# H3_DDR3.net
KiCad netlist of a schematic drawn in Altium Designer
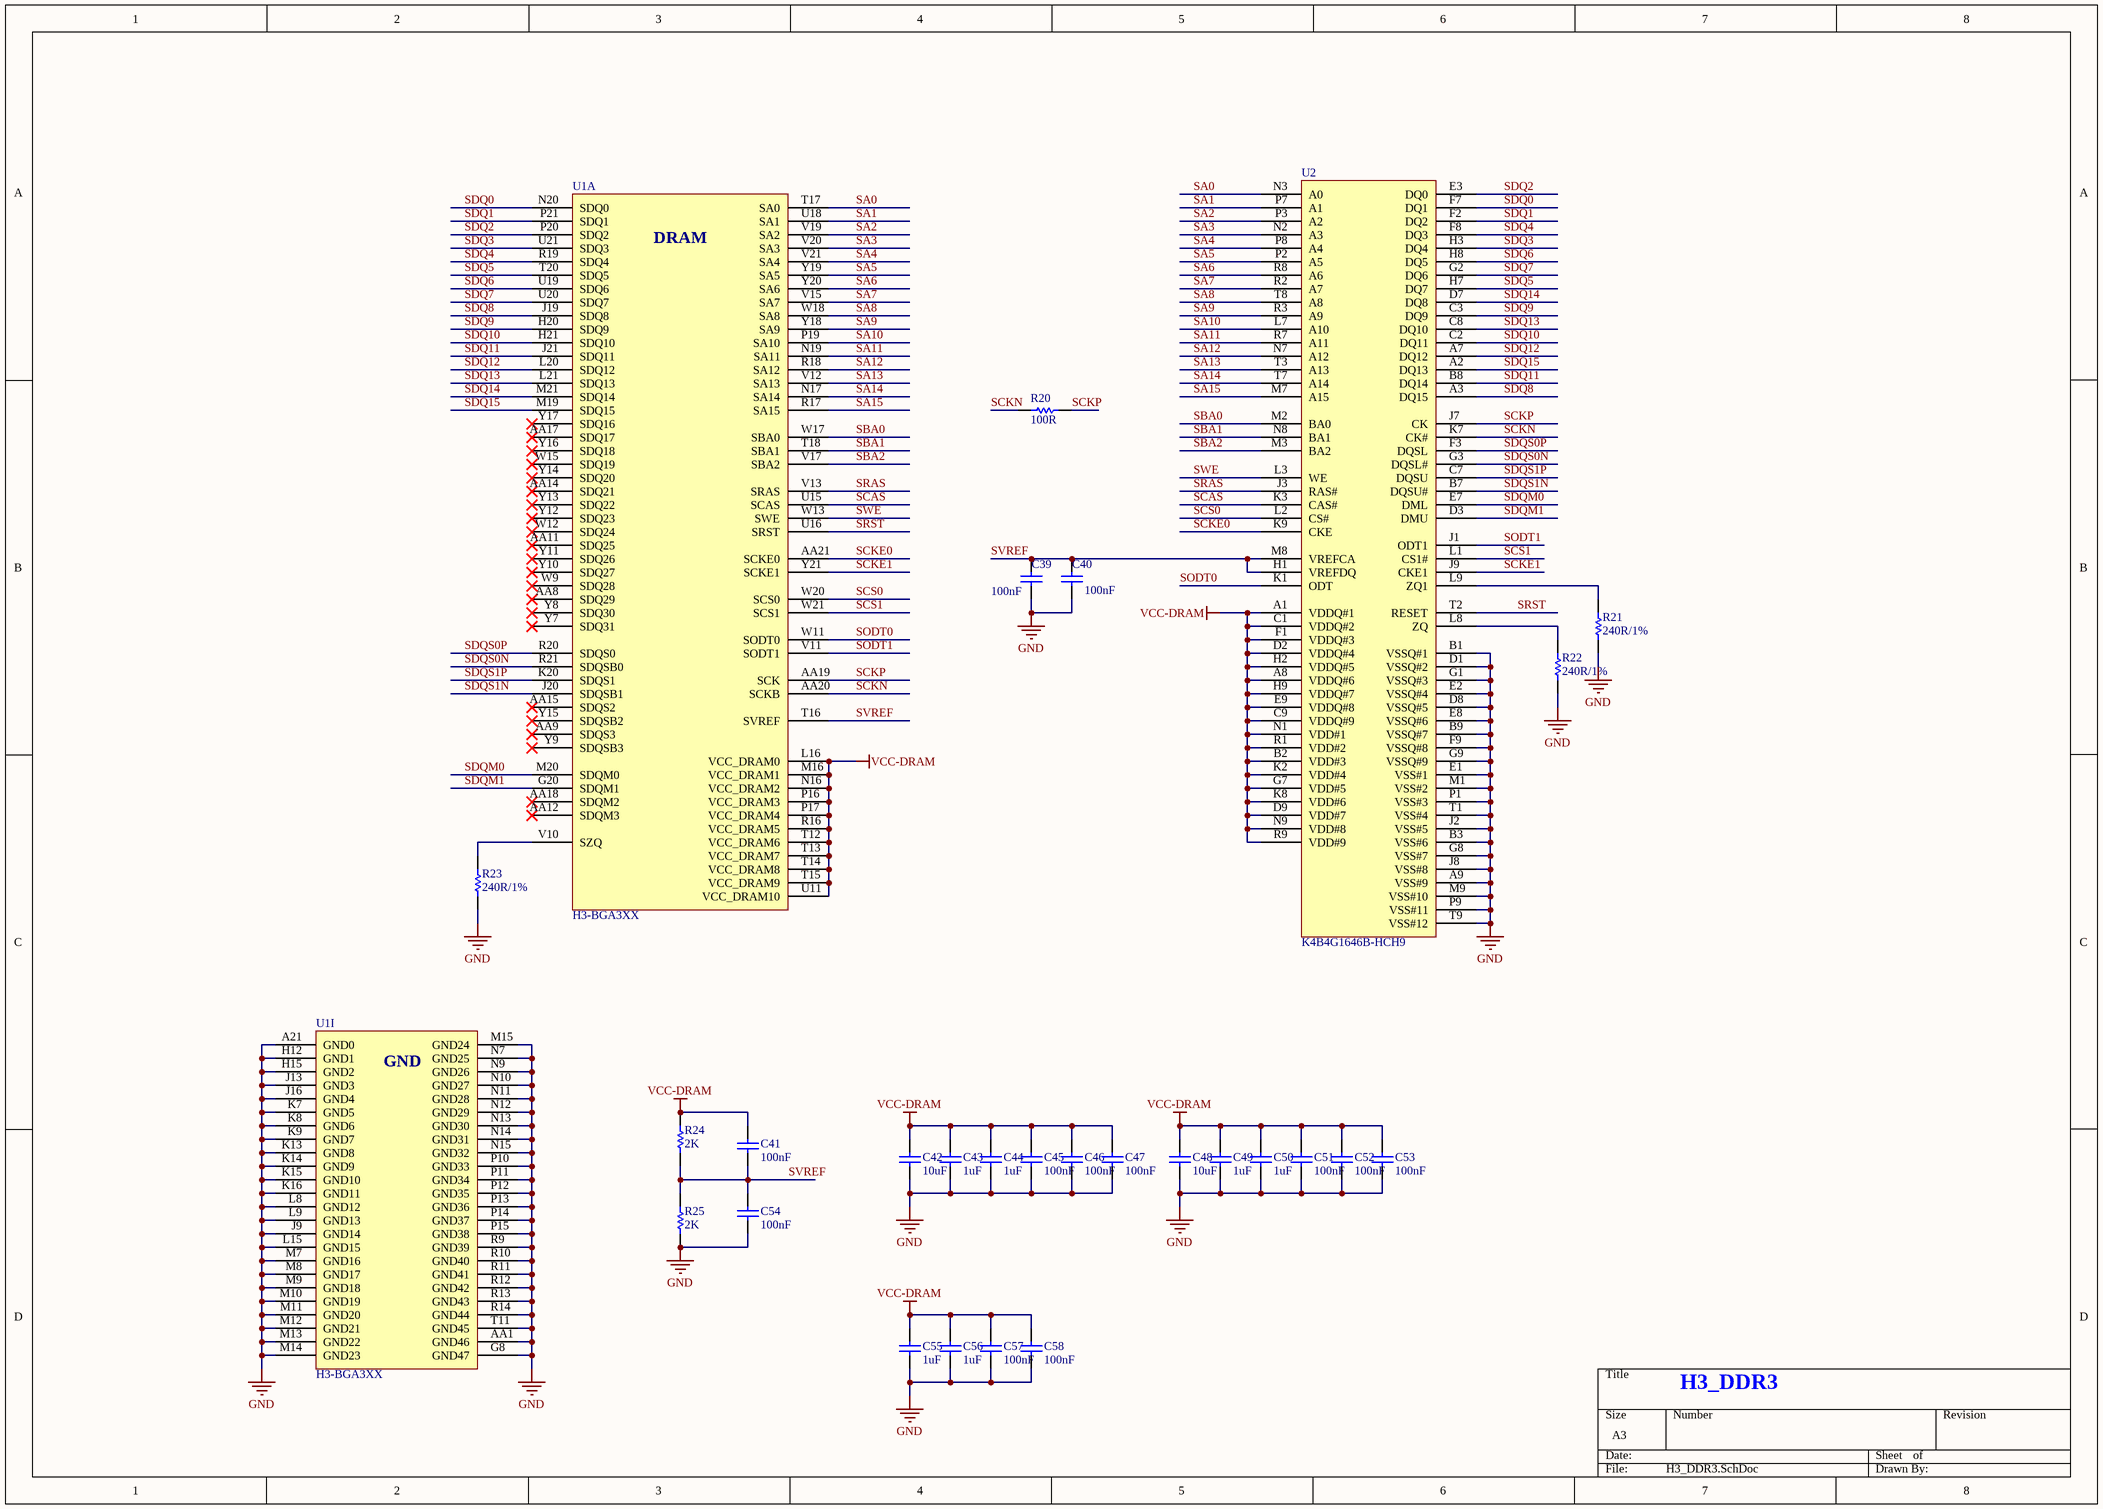
[diagram p0: H3_DDR3.SchDoc]

(export (version "E")
  (design (tool "Eeschema 10.0.6"))
  (components
    (comp (ref "C39")
      (value "100nF")
      (footprint "H3_Core:C0402")
      (description "电容")
      (fields (field (name "PUBLISHER") "Altium Limited"))
      (libsource (lib "Devices") (part "C0402"))
    )
    (comp (ref "C40")
      (value "100nF")
      (footprint "H3_Core:C0402")
      (description "电容")
      (fields (field (name "PUBLISHER") "Altium Limited"))
      (libsource (lib "Devices") (part "C0402"))
    )
    (comp (ref "C41")
      (value "100nF")
      (footprint "H3_Core:C0402")
      (description "电容")
      (fields (field (name "PUBLISHER") "Altium Limited"))
      (libsource (lib "Devices") (part "C0402"))
    )
    (comp (ref "C42")
      (value "10uF")
      (footprint "H3_Core:C0603")
      (description "电容")
      (fields (field (name "PUBLISHER") "Altium Limited"))
      (libsource (lib "Devices") (part "C0603"))
    )
    (comp (ref "C43")
      (value "1uF")
      (footprint "H3_Core:C0402")
      (description "电容")
      (fields (field (name "PUBLISHER") "Altium Limited"))
      (libsource (lib "Devices") (part "C0402"))
    )
    (comp (ref "C44")
      (value "1uF")
      (footprint "H3_Core:C0402")
      (description "电容")
      (fields (field (name "PUBLISHER") "Altium Limited"))
      (libsource (lib "Devices") (part "C0402"))
    )
    (comp (ref "C45")
      (value "100nF")
      (footprint "H3_Core:C0402")
      (description "电容")
      (fields (field (name "PUBLISHER") "Altium Limited"))
      (libsource (lib "Devices") (part "C0402"))
    )
    (comp (ref "C46")
      (value "100nF")
      (footprint "H3_Core:C0402")
      (description "电容")
      (fields (field (name "PUBLISHER") "Altium Limited"))
      (libsource (lib "Devices") (part "C0402"))
    )
    (comp (ref "C47")
      (value "100nF")
      (footprint "H3_Core:C0402")
      (description "电容")
      (fields (field (name "PUBLISHER") "Altium Limited"))
      (libsource (lib "Devices") (part "C0402"))
    )
    (comp (ref "C48")
      (value "10uF")
      (footprint "H3_Core:C0603")
      (description "电容")
      (fields (field (name "PUBLISHER") "Altium Limited"))
      (libsource (lib "Devices") (part "C0603"))
    )
    (comp (ref "C49")
      (value "1uF")
      (footprint "H3_Core:C0402")
      (description "电容")
      (fields (field (name "PUBLISHER") "Altium Limited"))
      (libsource (lib "Devices") (part "C0402"))
    )
    (comp (ref "C50")
      (value "1uF")
      (footprint "H3_Core:C0402")
      (description "电容")
      (fields (field (name "PUBLISHER") "Altium Limited"))
      (libsource (lib "Devices") (part "C0402"))
    )
    (comp (ref "C51")
      (value "100nF")
      (footprint "H3_Core:C0402")
      (description "电容")
      (fields (field (name "PUBLISHER") "Altium Limited"))
      (libsource (lib "Devices") (part "C0402"))
    )
    (comp (ref "C52")
      (value "100nF")
      (footprint "H3_Core:C0402")
      (description "电容")
      (fields (field (name "PUBLISHER") "Altium Limited"))
      (libsource (lib "Devices") (part "C0402"))
    )
    (comp (ref "C53")
      (value "100nF")
      (footprint "H3_Core:C0402")
      (description "电容")
      (fields (field (name "PUBLISHER") "Altium Limited"))
      (libsource (lib "Devices") (part "C0402"))
    )
    (comp (ref "C54")
      (value "100nF")
      (footprint "H3_Core:C0402")
      (description "电容")
      (fields (field (name "PUBLISHER") "Altium Limited"))
      (libsource (lib "Devices") (part "C0402"))
    )
    (comp (ref "C55")
      (value "1uF")
      (footprint "H3_Core:C0402")
      (description "电容")
      (fields (field (name "PUBLISHER") "Altium Limited"))
      (libsource (lib "Devices") (part "C0402"))
    )
    (comp (ref "C56")
      (value "1uF")
      (footprint "H3_Core:C0402")
      (description "电容")
      (fields (field (name "PUBLISHER") "Altium Limited"))
      (libsource (lib "Devices") (part "C0402"))
    )
    (comp (ref "C57")
      (value "100nF")
      (footprint "H3_Core:C0402")
      (description "电容")
      (fields (field (name "PUBLISHER") "Altium Limited"))
      (libsource (lib "Devices") (part "C0402"))
    )
    (comp (ref "C58")
      (value "100nF")
      (footprint "H3_Core:C0402")
      (description "电容")
      (fields (field (name "PUBLISHER") "Altium Limited"))
      (libsource (lib "Devices") (part "C0402"))
    )
    (comp (ref "R20")
      (value "100R")
      (footprint "H3_Core:R0402")
      (description "电阻")
      (fields (field (name "PUBLISHER") "Altium Limited"))
      (libsource (lib "Devices") (part "RES0402"))
    )
    (comp (ref "R21")
      (value "240R/1%")
      (footprint "H3_Core:R0402")
      (description "电阻")
      (fields (field (name "PUBLISHER") "Altium Limited"))
      (libsource (lib "Devices") (part "RES0402"))
    )
    (comp (ref "R22")
      (value "240R/1%")
      (footprint "H3_Core:R0402")
      (description "电阻")
      (fields (field (name "PUBLISHER") "Altium Limited"))
      (libsource (lib "Devices") (part "RES0402"))
    )
    (comp (ref "R23")
      (value "240R/1%")
      (footprint "H3_Core:R0402")
      (description "电阻")
      (fields (field (name "PUBLISHER") "Altium Limited"))
      (libsource (lib "Devices") (part "RES0402"))
    )
    (comp (ref "R24")
      (value "2K")
      (footprint "H3_Core:R0402")
      (description "电阻")
      (fields (field (name "PUBLISHER") "Altium Limited"))
      (libsource (lib "Devices") (part "RES0402"))
    )
    (comp (ref "R25")
      (value "2K")
      (footprint "H3_Core:R0402")
      (description "电阻")
      (fields (field (name "PUBLISHER") "Altium Limited"))
      (libsource (lib "Devices") (part "RES0402"))
    )
    (comp (ref "U1") (value "H3-BGA3XX") (footprint "BGA-H3-347") (libsource (lib "IC") (part "H3-BGA3XX")))
    (comp (ref "U2")
      (value "K4B4G1646B-HCH9")
      (footprint "FBGA-96")
      (libsource (lib "IC") (part "K4B4G1646B-HCH9"))
    )
  )
  (nets
    (net (code "1") (name "/SA0") (class "Default")
      (node (ref "U1") (pin "T17") (pinfunction "SA0_T17") (pintype "passive"))
      (node (ref "U2") (pin "N3") (pinfunction "A0_N3") (pintype "passive"))
    )
    (net (code "2") (name "/SA1") (class "Default")
      (node (ref "U1") (pin "U18") (pinfunction "SA1_U18") (pintype "passive"))
      (node (ref "U2") (pin "P7") (pinfunction "A1_P7") (pintype "passive"))
    )
    (net (code "3") (name "/SA2") (class "Default")
      (node (ref "U1") (pin "V19") (pinfunction "SA2_V19") (pintype "passive"))
      (node (ref "U2") (pin "P3") (pinfunction "A2_P3") (pintype "passive"))
    )
    (net (code "4") (name "/SA3") (class "Default")
      (node (ref "U1") (pin "V20") (pinfunction "SA3_V20") (pintype "passive"))
      (node (ref "U2") (pin "N2") (pinfunction "A3_N2") (pintype "passive"))
    )
    (net (code "5") (name "/SA4") (class "Default")
      (node (ref "U1") (pin "V21") (pinfunction "SA4_V21") (pintype "passive"))
      (node (ref "U2") (pin "P8") (pinfunction "A4_P8") (pintype "passive"))
    )
    (net (code "6") (name "/SA5") (class "Default")
      (node (ref "U1") (pin "Y19") (pinfunction "SA5_Y19") (pintype "passive"))
      (node (ref "U2") (pin "P2") (pinfunction "A5_P2") (pintype "passive"))
    )
    (net (code "7") (name "/SA6") (class "Default")
      (node (ref "U1") (pin "Y20") (pinfunction "SA6_Y20") (pintype "passive"))
      (node (ref "U2") (pin "R8") (pinfunction "A6_R8") (pintype "passive"))
    )
    (net (code "8") (name "/SA7") (class "Default")
      (node (ref "U1") (pin "V15") (pinfunction "SA7_V15") (pintype "passive"))
      (node (ref "U2") (pin "R2") (pinfunction "A7_R2") (pintype "passive"))
    )
    (net (code "9") (name "/SA8") (class "Default")
      (node (ref "U1") (pin "W18") (pinfunction "SA8_W18") (pintype "passive"))
      (node (ref "U2") (pin "T8") (pinfunction "A8_T8") (pintype "passive"))
    )
    (net (code "10") (name "/SA9") (class "Default")
      (node (ref "U1") (pin "Y18") (pinfunction "SA9_Y18") (pintype "passive"))
      (node (ref "U2") (pin "R3") (pinfunction "A9_R3") (pintype "passive"))
    )
    (net (code "11") (name "/SA10") (class "Default")
      (node (ref "U1") (pin "P19") (pinfunction "SA10_P19") (pintype "passive"))
      (node (ref "U2") (pin "L7") (pinfunction "A10_L7") (pintype "passive"))
    )
    (net (code "12") (name "/SA11") (class "Default")
      (node (ref "U1") (pin "N19") (pinfunction "SA11_N19") (pintype "passive"))
      (node (ref "U2") (pin "R7") (pinfunction "A11_R7") (pintype "passive"))
    )
    (net (code "13") (name "/SA12") (class "Default")
      (node (ref "U1") (pin "R18") (pinfunction "SA12_R18") (pintype "passive"))
      (node (ref "U2") (pin "N7") (pinfunction "A12_N7") (pintype "passive"))
    )
    (net (code "14") (name "/SA13") (class "Default")
      (node (ref "U1") (pin "V12") (pinfunction "SA13_V12") (pintype "passive"))
      (node (ref "U2") (pin "T3") (pinfunction "A13_T3") (pintype "passive"))
    )
    (net (code "15") (name "/SA14") (class "Default")
      (node (ref "U1") (pin "N17") (pinfunction "SA14_N17") (pintype "passive"))
      (node (ref "U2") (pin "T7") (pinfunction "A14_T7") (pintype "passive"))
    )
    (net (code "16") (name "/SA15") (class "Default")
      (node (ref "U1") (pin "R17") (pinfunction "SA15_R17") (pintype "passive"))
      (node (ref "U2") (pin "M7") (pinfunction "A15_M7") (pintype "passive"))
    )
    (net (code "17") (name "/SBA0") (class "Default")
      (node (ref "U1") (pin "W17") (pinfunction "SBA0_W17") (pintype "passive"))
      (node (ref "U2") (pin "M2") (pinfunction "BA0_M2") (pintype "passive"))
    )
    (net (code "18") (name "/SBA1") (class "Default")
      (node (ref "U1") (pin "T18") (pinfunction "SBA1_T18") (pintype "passive"))
      (node (ref "U2") (pin "N8") (pinfunction "BA1_N8") (pintype "passive"))
    )
    (net (code "19") (name "/SBA2") (class "Default")
      (node (ref "U1") (pin "V17") (pinfunction "SBA2_V17") (pintype "passive"))
      (node (ref "U2") (pin "M3") (pinfunction "BA2_M3") (pintype "passive"))
    )
    (net (code "20") (name "/SCAS") (class "Default")
      (node (ref "U1") (pin "U15") (pinfunction "SCAS_U15") (pintype "passive"))
      (node (ref "U2") (pin "K3") (pinfunction "CAS#_K3") (pintype "passive"))
    )
    (net (code "21") (name "/SCKE0") (class "Default")
      (node (ref "U1") (pin "AA21") (pinfunction "SCKE0_AA21") (pintype "passive"))
      (node (ref "U2") (pin "K9") (pinfunction "CKE_K9") (pintype "passive"))
    )
    (net (code "22") (name "/SCKE1") (class "Default")
      (node (ref "U1") (pin "Y21") (pinfunction "SCKE1_Y21") (pintype "passive"))
      (node (ref "U2") (pin "J9") (pinfunction "CKE1_J9") (pintype "passive"))
    )
    (net (code "23") (name "/SCKN") (class "Default")
      (node (ref "R20") (pin "2") (pinfunction "2_2") (pintype "passive"))
      (node (ref "U1") (pin "AA20") (pinfunction "SCKB_AA20") (pintype "passive"))
      (node (ref "U2") (pin "K7") (pinfunction "CK#_K7") (pintype "passive"))
    )
    (net (code "24") (name "/SCKP") (class "Default")
      (node (ref "R20") (pin "1") (pinfunction "1_1") (pintype "passive"))
      (node (ref "U1") (pin "AA19") (pinfunction "SCK_AA19") (pintype "passive"))
      (node (ref "U2") (pin "J7") (pinfunction "CK_J7") (pintype "passive"))
    )
    (net (code "25") (name "/SCS0") (class "Default")
      (node (ref "U1") (pin "W20") (pinfunction "SCS0_W20") (pintype "passive"))
      (node (ref "U2") (pin "L2") (pinfunction "CS#_L2") (pintype "passive"))
    )
    (net (code "26") (name "/SCS1") (class "Default")
      (node (ref "U1") (pin "W21") (pinfunction "SCS1_W21") (pintype "passive"))
      (node (ref "U2") (pin "L1") (pinfunction "CS1#_L1") (pintype "passive"))
    )
    (net (code "27") (name "/SDQ0") (class "Default")
      (node (ref "U1") (pin "N20") (pinfunction "SDQ0_N20") (pintype "passive"))
      (node (ref "U2") (pin "F7") (pinfunction "DQ1_F7") (pintype "passive"))
    )
    (net (code "28") (name "/SDQ1") (class "Default")
      (node (ref "U1") (pin "P21") (pinfunction "SDQ1_P21") (pintype "passive"))
      (node (ref "U2") (pin "F2") (pinfunction "DQ2_F2") (pintype "passive"))
    )
    (net (code "29") (name "/SDQ2") (class "Default")
      (node (ref "U1") (pin "P20") (pinfunction "SDQ2_P20") (pintype "passive"))
      (node (ref "U2") (pin "E3") (pinfunction "DQ0_E3") (pintype "passive"))
    )
    (net (code "30") (name "/SDQ3") (class "Default")
      (node (ref "U1") (pin "U21") (pinfunction "SDQ3_U21") (pintype "passive"))
      (node (ref "U2") (pin "H3") (pinfunction "DQ4_H3") (pintype "passive"))
    )
    (net (code "31") (name "/SDQ4") (class "Default")
      (node (ref "U1") (pin "R19") (pinfunction "SDQ4_R19") (pintype "passive"))
      (node (ref "U2") (pin "F8") (pinfunction "DQ3_F8") (pintype "passive"))
    )
    (net (code "32") (name "/SDQ5") (class "Default")
      (node (ref "U1") (pin "T20") (pinfunction "SDQ5_T20") (pintype "passive"))
      (node (ref "U2") (pin "H7") (pinfunction "DQ7_H7") (pintype "passive"))
    )
    (net (code "33") (name "/SDQ6") (class "Default")
      (node (ref "U1") (pin "U19") (pinfunction "SDQ6_U19") (pintype "passive"))
      (node (ref "U2") (pin "H8") (pinfunction "DQ5_H8") (pintype "passive"))
    )
    (net (code "34") (name "/SDQ7") (class "Default")
      (node (ref "U1") (pin "U20") (pinfunction "SDQ7_U20") (pintype "passive"))
      (node (ref "U2") (pin "G2") (pinfunction "DQ6_G2") (pintype "passive"))
    )
    (net (code "35") (name "/SDQ8") (class "Default")
      (node (ref "U1") (pin "J19") (pinfunction "SDQ8_J19") (pintype "passive"))
      (node (ref "U2") (pin "A3") (pinfunction "DQ15_A3") (pintype "passive"))
    )
    (net (code "36") (name "/SDQ9") (class "Default")
      (node (ref "U1") (pin "H20") (pinfunction "SDQ9_H20") (pintype "passive"))
      (node (ref "U2") (pin "C3") (pinfunction "DQ9_C3") (pintype "passive"))
    )
    (net (code "37") (name "/SDQ10") (class "Default")
      (node (ref "U1") (pin "H21") (pinfunction "SDQ10_H21") (pintype "passive"))
      (node (ref "U2") (pin "C2") (pinfunction "DQ11_C2") (pintype "passive"))
    )
    (net (code "38") (name "/SDQ11") (class "Default")
      (node (ref "U1") (pin "J21") (pinfunction "SDQ11_J21") (pintype "passive"))
      (node (ref "U2") (pin "B8") (pinfunction "DQ14_B8") (pintype "passive"))
    )
    (net (code "39") (name "/SDQ12") (class "Default")
      (node (ref "U1") (pin "L20") (pinfunction "SDQ12_L20") (pintype "passive"))
      (node (ref "U2") (pin "A7") (pinfunction "DQ12_A7") (pintype "passive"))
    )
    (net (code "40") (name "/SDQ13") (class "Default")
      (node (ref "U1") (pin "L21") (pinfunction "SDQ13_L21") (pintype "passive"))
      (node (ref "U2") (pin "C8") (pinfunction "DQ10_C8") (pintype "passive"))
    )
    (net (code "41") (name "/SDQ14") (class "Default")
      (node (ref "U1") (pin "M21") (pinfunction "SDQ14_M21") (pintype "passive"))
      (node (ref "U2") (pin "D7") (pinfunction "DQ8_D7") (pintype "passive"))
    )
    (net (code "42") (name "/SDQ15") (class "Default")
      (node (ref "U1") (pin "M19") (pinfunction "SDQ15_M19") (pintype "passive"))
      (node (ref "U2") (pin "A2") (pinfunction "DQ13_A2") (pintype "passive"))
    )
    (net (code "43") (name "/SDQM0") (class "Default")
      (node (ref "U1") (pin "M20") (pinfunction "SDQM0_M20") (pintype "passive"))
      (node (ref "U2") (pin "E7") (pinfunction "DML_E7") (pintype "passive"))
    )
    (net (code "44") (name "/SDQM1") (class "Default")
      (node (ref "U1") (pin "G20") (pinfunction "SDQM1_G20") (pintype "passive"))
      (node (ref "U2") (pin "D3") (pinfunction "DMU_D3") (pintype "passive"))
    )
    (net (code "45") (name "/SDQS0N") (class "Default")
      (node (ref "U1") (pin "R21") (pinfunction "SDQSB0_R21") (pintype "passive"))
      (node (ref "U2") (pin "G3") (pinfunction "DQSL#_G3") (pintype "passive"))
    )
    (net (code "46") (name "/SDQS0P") (class "Default")
      (node (ref "U1") (pin "R20") (pinfunction "SDQS0_R20") (pintype "passive"))
      (node (ref "U2") (pin "F3") (pinfunction "DQSL_F3") (pintype "passive"))
    )
    (net (code "47") (name "/SDQS1N") (class "Default")
      (node (ref "U1") (pin "J20") (pinfunction "SDQSB1_J20") (pintype "passive"))
      (node (ref "U2") (pin "B7") (pinfunction "DQSU#_B7") (pintype "passive"))
    )
    (net (code "48") (name "/SDQS1P") (class "Default")
      (node (ref "U1") (pin "K20") (pinfunction "SDQS1_K20") (pintype "passive"))
      (node (ref "U2") (pin "C7") (pinfunction "DQSU_C7") (pintype "passive"))
    )
    (net (code "49") (name "/SODT0") (class "Default")
      (node (ref "U1") (pin "W11") (pinfunction "SODT0_W11") (pintype "passive"))
      (node (ref "U2") (pin "K1") (pinfunction "ODT_K1") (pintype "passive"))
    )
    (net (code "50") (name "/SODT1") (class "Default")
      (node (ref "U1") (pin "V11") (pinfunction "SODT1_V11") (pintype "passive"))
      (node (ref "U2") (pin "J1") (pinfunction "ODT1_J1") (pintype "passive"))
    )
    (net (code "51") (name "/SRAS") (class "Default")
      (node (ref "U1") (pin "V13") (pinfunction "SRAS_V13") (pintype "passive"))
      (node (ref "U2") (pin "J3") (pinfunction "RAS#_J3") (pintype "passive"))
    )
    (net (code "52") (name "/SRST") (class "Default")
      (node (ref "U1") (pin "U16") (pinfunction "SRST_U16") (pintype "passive"))
      (node (ref "U2") (pin "T2") (pinfunction "RESET_T2") (pintype "passive"))
    )
    (net (code "53") (name "/SVREF") (class "Default")
      (node (ref "C39") (pin "2") (pinfunction "2_2") (pintype "passive"))
      (node (ref "C40") (pin "2") (pinfunction "2_2") (pintype "passive"))
      (node (ref "C41") (pin "1") (pinfunction "1_1") (pintype "passive"))
      (node (ref "C54") (pin "2") (pinfunction "2_2") (pintype "passive"))
      (node (ref "R24") (pin "2") (pinfunction "2_2") (pintype "passive"))
      (node (ref "R25") (pin "1") (pinfunction "1_1") (pintype "passive"))
      (node (ref "U1") (pin "T16") (pinfunction "SVREF_T16") (pintype "passive"))
      (node (ref "U2") (pin "H1") (pinfunction "VREFDQ_H1") (pintype "passive"))
      (node (ref "U2") (pin "M8") (pinfunction "VREFCA_M8") (pintype "passive"))
    )
    (net (code "54") (name "/SWE") (class "Default")
      (node (ref "U1") (pin "W13") (pinfunction "SWE_W13") (pintype "passive"))
      (node (ref "U2") (pin "L3") (pinfunction "WE_L3") (pintype "passive"))
    )
    (net (code "55") (name "GND") (class "Default")
      (node (ref "C39") (pin "1") (pinfunction "1_1") (pintype "passive"))
      (node (ref "C40") (pin "1") (pinfunction "1_1") (pintype "passive"))
      (node (ref "C42") (pin "1") (pinfunction "1_1") (pintype "passive"))
      (node (ref "C43") (pin "1") (pinfunction "1_1") (pintype "passive"))
      (node (ref "C44") (pin "1") (pinfunction "1_1") (pintype "passive"))
      (node (ref "C45") (pin "1") (pinfunction "1_1") (pintype "passive"))
      (node (ref "C46") (pin "1") (pinfunction "1_1") (pintype "passive"))
      (node (ref "C47") (pin "1") (pinfunction "1_1") (pintype "passive"))
      (node (ref "C48") (pin "1") (pinfunction "1_1") (pintype "passive"))
      (node (ref "C49") (pin "1") (pinfunction "1_1") (pintype "passive"))
      (node (ref "C50") (pin "1") (pinfunction "1_1") (pintype "passive"))
      (node (ref "C51") (pin "1") (pinfunction "1_1") (pintype "passive"))
      (node (ref "C52") (pin "1") (pinfunction "1_1") (pintype "passive"))
      (node (ref "C53") (pin "1") (pinfunction "1_1") (pintype "passive"))
      (node (ref "C54") (pin "1") (pinfunction "1_1") (pintype "passive"))
      (node (ref "C55") (pin "1") (pinfunction "1_1") (pintype "passive"))
      (node (ref "C56") (pin "1") (pinfunction "1_1") (pintype "passive"))
      (node (ref "C57") (pin "1") (pinfunction "1_1") (pintype "passive"))
      (node (ref "C58") (pin "1") (pinfunction "1_1") (pintype "passive"))
      (node (ref "R21") (pin "1") (pinfunction "1_1") (pintype "passive"))
      (node (ref "R22") (pin "1") (pinfunction "1_1") (pintype "passive"))
      (node (ref "R23") (pin "1") (pinfunction "1_1") (pintype "passive"))
      (node (ref "R25") (pin "2") (pinfunction "2_2") (pintype "passive"))
      (node (ref "U1") (pin "A21") (pinfunction "GND0_A21") (pintype "passive"))
      (node (ref "U1") (pin "AA1") (pinfunction "GND46_AA1") (pintype "passive"))
      (node (ref "U1") (pin "G8") (pinfunction "GND47_G8") (pintype "passive"))
      (node (ref "U1") (pin "H12") (pinfunction "GND1_H12") (pintype "passive"))
      (node (ref "U1") (pin "H15") (pinfunction "GND2_H15") (pintype "passive"))
      (node (ref "U1") (pin "J13") (pinfunction "GND3_J13") (pintype "passive"))
      (node (ref "U1") (pin "J16") (pinfunction "GND4_J16") (pintype "passive"))
      (node (ref "U1") (pin "J9") (pinfunction "GND14_J9") (pintype "passive"))
      (node (ref "U1") (pin "K13") (pinfunction "GND8_K13") (pintype "passive"))
      (node (ref "U1") (pin "K14") (pinfunction "GND9_K14") (pintype "passive"))
      (node (ref "U1") (pin "K15") (pinfunction "GND10_K15") (pintype "passive"))
      (node (ref "U1") (pin "K16") (pinfunction "GND11_K16") (pintype "passive"))
      (node (ref "U1") (pin "K7") (pinfunction "GND5_K7") (pintype "passive"))
      (node (ref "U1") (pin "K8") (pinfunction "GND6_K8") (pintype "passive"))
      (node (ref "U1") (pin "K9") (pinfunction "GND7_K9") (pintype "passive"))
      (node (ref "U1") (pin "L15") (pinfunction "GND15_L15") (pintype "passive"))
      (node (ref "U1") (pin "L8") (pinfunction "GND12_L8") (pintype "passive"))
      (node (ref "U1") (pin "L9") (pinfunction "GND13_L9") (pintype "passive"))
      (node (ref "U1") (pin "M10") (pinfunction "GND19_M10") (pintype "passive"))
      (node (ref "U1") (pin "M11") (pinfunction "GND20_M11") (pintype "passive"))
      (node (ref "U1") (pin "M12") (pinfunction "GND21_M12") (pintype "passive"))
      (node (ref "U1") (pin "M13") (pinfunction "GND22_M13") (pintype "passive"))
      (node (ref "U1") (pin "M14") (pinfunction "GND23_M14") (pintype "passive"))
      (node (ref "U1") (pin "M15") (pinfunction "GND24_M15") (pintype "passive"))
      (node (ref "U1") (pin "M7") (pinfunction "GND16_M7") (pintype "passive"))
      (node (ref "U1") (pin "M8") (pinfunction "GND17_M8") (pintype "passive"))
      (node (ref "U1") (pin "M9") (pinfunction "GND18_M9") (pintype "passive"))
      (node (ref "U1") (pin "N10") (pinfunction "GND27_N10") (pintype "passive"))
      (node (ref "U1") (pin "N11") (pinfunction "GND28_N11") (pintype "passive"))
      (node (ref "U1") (pin "N12") (pinfunction "GND29_N12") (pintype "passive"))
      (node (ref "U1") (pin "N13") (pinfunction "GND30_N13") (pintype "passive"))
      (node (ref "U1") (pin "N14") (pinfunction "GND31_N14") (pintype "passive"))
      (node (ref "U1") (pin "N15") (pinfunction "GND32_N15") (pintype "passive"))
      (node (ref "U1") (pin "N7") (pinfunction "GND25_N7") (pintype "passive"))
      (node (ref "U1") (pin "N9") (pinfunction "GND26_N9") (pintype "passive"))
      (node (ref "U1") (pin "P10") (pinfunction "GND33_P10") (pintype "passive"))
      (node (ref "U1") (pin "P11") (pinfunction "GND34_P11") (pintype "passive"))
      (node (ref "U1") (pin "P12") (pinfunction "GND35_P12") (pintype "passive"))
      (node (ref "U1") (pin "P13") (pinfunction "GND36_P13") (pintype "passive"))
      (node (ref "U1") (pin "P14") (pinfunction "GND37_P14") (pintype "passive"))
      (node (ref "U1") (pin "P15") (pinfunction "GND38_P15") (pintype "passive"))
      (node (ref "U1") (pin "R10") (pinfunction "GND40_R10") (pintype "passive"))
      (node (ref "U1") (pin "R11") (pinfunction "GND41_R11") (pintype "passive"))
      (node (ref "U1") (pin "R12") (pinfunction "GND42_R12") (pintype "passive"))
      (node (ref "U1") (pin "R13") (pinfunction "GND43_R13") (pintype "passive"))
      (node (ref "U1") (pin "R14") (pinfunction "GND44_R14") (pintype "passive"))
      (node (ref "U1") (pin "R9") (pinfunction "GND39_R9") (pintype "passive"))
      (node (ref "U1") (pin "T11") (pinfunction "GND45_T11") (pintype "passive"))
      (node (ref "U2") (pin "A9") (pinfunction "VSS#9_A9") (pintype "passive"))
      (node (ref "U2") (pin "B1") (pinfunction "VSSQ#1_B1") (pintype "passive"))
      (node (ref "U2") (pin "B3") (pinfunction "VSS#6_B3") (pintype "passive"))
      (node (ref "U2") (pin "B9") (pinfunction "VSSQ#7_B9") (pintype "passive"))
      (node (ref "U2") (pin "D1") (pinfunction "VSSQ#2_D1") (pintype "passive"))
      (node (ref "U2") (pin "D8") (pinfunction "VSSQ#5_D8") (pintype "passive"))
      (node (ref "U2") (pin "E1") (pinfunction "VSS#1_E1") (pintype "passive"))
      (node (ref "U2") (pin "E2") (pinfunction "VSSQ#4_E2") (pintype "passive"))
      (node (ref "U2") (pin "E8") (pinfunction "VSSQ#6_E8") (pintype "passive"))
      (node (ref "U2") (pin "F9") (pinfunction "VSSQ#8_F9") (pintype "passive"))
      (node (ref "U2") (pin "G1") (pinfunction "VSSQ#3_G1") (pintype "passive"))
      (node (ref "U2") (pin "G8") (pinfunction "VSS#7_G8") (pintype "passive"))
      (node (ref "U2") (pin "G9") (pinfunction "VSSQ#9_G9") (pintype "passive"))
      (node (ref "U2") (pin "J2") (pinfunction "VSS#5_J2") (pintype "passive"))
      (node (ref "U2") (pin "J8") (pinfunction "VSS#8_J8") (pintype "passive"))
      (node (ref "U2") (pin "M1") (pinfunction "VSS#2_M1") (pintype "passive"))
      (node (ref "U2") (pin "M9") (pinfunction "VSS#10_M9") (pintype "passive"))
      (node (ref "U2") (pin "P1") (pinfunction "VSS#3_P1") (pintype "passive"))
      (node (ref "U2") (pin "P9") (pinfunction "VSS#11_P9") (pintype "passive"))
      (node (ref "U2") (pin "T1") (pinfunction "VSS#4_T1") (pintype "passive"))
      (node (ref "U2") (pin "T9") (pinfunction "VSS#12_T9") (pintype "passive"))
    )
    (net (code "56") (name "Net-(U1A-SZQ)") (class "Default")
      (node (ref "R23") (pin "2") (pinfunction "2_2") (pintype "passive"))
      (node (ref "U1") (pin "V10") (pinfunction "SZQ_V10") (pintype "passive"))
    )
    (net (code "57") (name "Net-(U2-ZQ)") (class "Default")
      (node (ref "R22") (pin "2") (pinfunction "2_2") (pintype "passive"))
      (node (ref "U2") (pin "L8") (pinfunction "ZQ_L8") (pintype "passive"))
    )
    (net (code "58") (name "Net-(U2-ZQ1)") (class "Default")
      (node (ref "R21") (pin "2") (pinfunction "2_2") (pintype "passive"))
      (node (ref "U2") (pin "L9") (pinfunction "ZQ1_L9") (pintype "passive"))
    )
    (net (code "59") (name "VCC-DRAM") (class "Default")
      (node (ref "C41") (pin "2") (pinfunction "2_2") (pintype "passive"))
      (node (ref "C42") (pin "2") (pinfunction "2_2") (pintype "passive"))
      (node (ref "C43") (pin "2") (pinfunction "2_2") (pintype "passive"))
      (node (ref "C44") (pin "2") (pinfunction "2_2") (pintype "passive"))
      (node (ref "C45") (pin "2") (pinfunction "2_2") (pintype "passive"))
      (node (ref "C46") (pin "2") (pinfunction "2_2") (pintype "passive"))
      (node (ref "C47") (pin "2") (pinfunction "2_2") (pintype "passive"))
      (node (ref "C48") (pin "2") (pinfunction "2_2") (pintype "passive"))
      (node (ref "C49") (pin "2") (pinfunction "2_2") (pintype "passive"))
      (node (ref "C50") (pin "2") (pinfunction "2_2") (pintype "passive"))
      (node (ref "C51") (pin "2") (pinfunction "2_2") (pintype "passive"))
      (node (ref "C52") (pin "2") (pinfunction "2_2") (pintype "passive"))
      (node (ref "C53") (pin "2") (pinfunction "2_2") (pintype "passive"))
      (node (ref "C55") (pin "2") (pinfunction "2_2") (pintype "passive"))
      (node (ref "C56") (pin "2") (pinfunction "2_2") (pintype "passive"))
      (node (ref "C57") (pin "2") (pinfunction "2_2") (pintype "passive"))
      (node (ref "C58") (pin "2") (pinfunction "2_2") (pintype "passive"))
      (node (ref "R24") (pin "1") (pinfunction "1_1") (pintype "passive"))
      (node (ref "U1") (pin "L16") (pinfunction "VCC_DRAM0_L16") (pintype "passive"))
      (node (ref "U1") (pin "M16") (pinfunction "VCC_DRAM1_M16") (pintype "passive"))
      (node (ref "U1") (pin "N16") (pinfunction "VCC_DRAM2_N16") (pintype "passive"))
      (node (ref "U1") (pin "P16") (pinfunction "VCC_DRAM3_P16") (pintype "passive"))
      (node (ref "U1") (pin "P17") (pinfunction "VCC_DRAM4_P17") (pintype "passive"))
      (node (ref "U1") (pin "R16") (pinfunction "VCC_DRAM5_R16") (pintype "passive"))
      (node (ref "U1") (pin "T12") (pinfunction "VCC_DRAM6_T12") (pintype "passive"))
      (node (ref "U1") (pin "T13") (pinfunction "VCC_DRAM7_T13") (pintype "passive"))
      (node (ref "U1") (pin "T14") (pinfunction "VCC_DRAM8_T14") (pintype "passive"))
      (node (ref "U1") (pin "T15") (pinfunction "VCC_DRAM9_T15") (pintype "passive"))
      (node (ref "U1") (pin "U11") (pinfunction "VCC_DRAM10_U11") (pintype "passive"))
      (node (ref "U2") (pin "A1") (pinfunction "VDDQ#1_A1") (pintype "passive"))
      (node (ref "U2") (pin "A8") (pinfunction "VDDQ#6_A8") (pintype "passive"))
      (node (ref "U2") (pin "B2") (pinfunction "VDD#3_B2") (pintype "passive"))
      (node (ref "U2") (pin "C1") (pinfunction "VDDQ#2_C1") (pintype "passive"))
      (node (ref "U2") (pin "C9") (pinfunction "VDDQ#9_C9") (pintype "passive"))
      (node (ref "U2") (pin "D2") (pinfunction "VDDQ#4_D2") (pintype "passive"))
      (node (ref "U2") (pin "D9") (pinfunction "VDD#7_D9") (pintype "passive"))
      (node (ref "U2") (pin "E9") (pinfunction "VDDQ#8_E9") (pintype "passive"))
      (node (ref "U2") (pin "F1") (pinfunction "VDDQ#3_F1") (pintype "passive"))
      (node (ref "U2") (pin "G7") (pinfunction "VDD#5_G7") (pintype "passive"))
      (node (ref "U2") (pin "H2") (pinfunction "VDDQ#5_H2") (pintype "passive"))
      (node (ref "U2") (pin "H9") (pinfunction "VDDQ#7_H9") (pintype "passive"))
      (node (ref "U2") (pin "K2") (pinfunction "VDD#4_K2") (pintype "passive"))
      (node (ref "U2") (pin "K8") (pinfunction "VDD#6_K8") (pintype "passive"))
      (node (ref "U2") (pin "N1") (pinfunction "VDD#1_N1") (pintype "passive"))
      (node (ref "U2") (pin "N9") (pinfunction "VDD#8_N9") (pintype "passive"))
      (node (ref "U2") (pin "R1") (pinfunction "VDD#2_R1") (pintype "passive"))
      (node (ref "U2") (pin "R9") (pinfunction "VDD#9_R9") (pintype "passive"))
    )
    (net (code "60") (name "unconnected-(U1A-SDQ16-PadY17)") (class "Default")
      (node (ref "U1") (pin "Y17") (pinfunction "SDQ16_Y17") (pintype "passive+no_connect"))
    )
    (net (code "61") (name "unconnected-(U1A-SDQ17-PadAA17)") (class "Default")
      (node (ref "U1") (pin "AA17") (pinfunction "SDQ17_AA17") (pintype "passive+no_connect"))
    )
    (net (code "62") (name "unconnected-(U1A-SDQ18-PadY16)") (class "Default")
      (node (ref "U1") (pin "Y16") (pinfunction "SDQ18_Y16") (pintype "passive+no_connect"))
    )
    (net (code "63") (name "unconnected-(U1A-SDQ19-PadW15)") (class "Default")
      (node (ref "U1") (pin "W15") (pinfunction "SDQ19_W15") (pintype "passive+no_connect"))
    )
    (net (code "64") (name "unconnected-(U1A-SDQ20-PadY14)") (class "Default")
      (node (ref "U1") (pin "Y14") (pinfunction "SDQ20_Y14") (pintype "passive+no_connect"))
    )
    (net (code "65") (name "unconnected-(U1A-SDQ21-PadAA14)") (class "Default")
      (node (ref "U1") (pin "AA14") (pinfunction "SDQ21_AA14") (pintype "passive+no_connect"))
    )
    (net (code "66") (name "unconnected-(U1A-SDQ22-PadY13)") (class "Default")
      (node (ref "U1") (pin "Y13") (pinfunction "SDQ22_Y13") (pintype "passive+no_connect"))
    )
    (net (code "67") (name "unconnected-(U1A-SDQ23-PadY12)") (class "Default")
      (node (ref "U1") (pin "Y12") (pinfunction "SDQ23_Y12") (pintype "passive+no_connect"))
    )
    (net (code "68") (name "unconnected-(U1A-SDQ24-PadW12)") (class "Default")
      (node (ref "U1") (pin "W12") (pinfunction "SDQ24_W12") (pintype "passive+no_connect"))
    )
    (net (code "69") (name "unconnected-(U1A-SDQ25-PadAA11)") (class "Default")
      (node (ref "U1") (pin "AA11") (pinfunction "SDQ25_AA11") (pintype "passive+no_connect"))
    )
    (net (code "70") (name "unconnected-(U1A-SDQ26-PadY11)") (class "Default")
      (node (ref "U1") (pin "Y11") (pinfunction "SDQ26_Y11") (pintype "passive+no_connect"))
    )
    (net (code "71") (name "unconnected-(U1A-SDQ27-PadY10)") (class "Default")
      (node (ref "U1") (pin "Y10") (pinfunction "SDQ27_Y10") (pintype "passive+no_connect"))
    )
    (net (code "72") (name "unconnected-(U1A-SDQ28-PadW9)") (class "Default")
      (node (ref "U1") (pin "W9") (pinfunction "SDQ28_W9") (pintype "passive+no_connect"))
    )
    (net (code "73") (name "unconnected-(U1A-SDQ29-PadAA8)") (class "Default")
      (node (ref "U1") (pin "AA8") (pinfunction "SDQ29_AA8") (pintype "passive+no_connect"))
    )
    (net (code "74") (name "unconnected-(U1A-SDQ30-PadY8)") (class "Default")
      (node (ref "U1") (pin "Y8") (pinfunction "SDQ30_Y8") (pintype "passive+no_connect"))
    )
    (net (code "75") (name "unconnected-(U1A-SDQ31-PadY7)") (class "Default")
      (node (ref "U1") (pin "Y7") (pinfunction "SDQ31_Y7") (pintype "passive+no_connect"))
    )
    (net (code "76") (name "unconnected-(U1A-SDQM2-PadAA18)") (class "Default")
      (node (ref "U1") (pin "AA18") (pinfunction "SDQM2_AA18") (pintype "passive+no_connect"))
    )
    (net (code "77") (name "unconnected-(U1A-SDQM3-PadAA12)") (class "Default")
      (node (ref "U1") (pin "AA12") (pinfunction "SDQM3_AA12") (pintype "passive+no_connect"))
    )
    (net (code "78") (name "unconnected-(U1A-SDQS2-PadAA15)") (class "Default")
      (node (ref "U1") (pin "AA15") (pinfunction "SDQS2_AA15") (pintype "passive+no_connect"))
    )
    (net (code "79") (name "unconnected-(U1A-SDQS3-PadAA9)") (class "Default")
      (node (ref "U1") (pin "AA9") (pinfunction "SDQS3_AA9") (pintype "passive+no_connect"))
    )
    (net (code "80") (name "unconnected-(U1A-SDQSB2-PadY15)") (class "Default")
      (node (ref "U1") (pin "Y15") (pinfunction "SDQSB2_Y15") (pintype "passive+no_connect"))
    )
    (net (code "81") (name "unconnected-(U1A-SDQSB3-PadY9)") (class "Default")
      (node (ref "U1") (pin "Y9") (pinfunction "SDQSB3_Y9") (pintype "passive+no_connect"))
    )
  )
)
